# Digital_Encoder_Breakout.net
KiCad netlist of a schematic drawn in Altium Designer
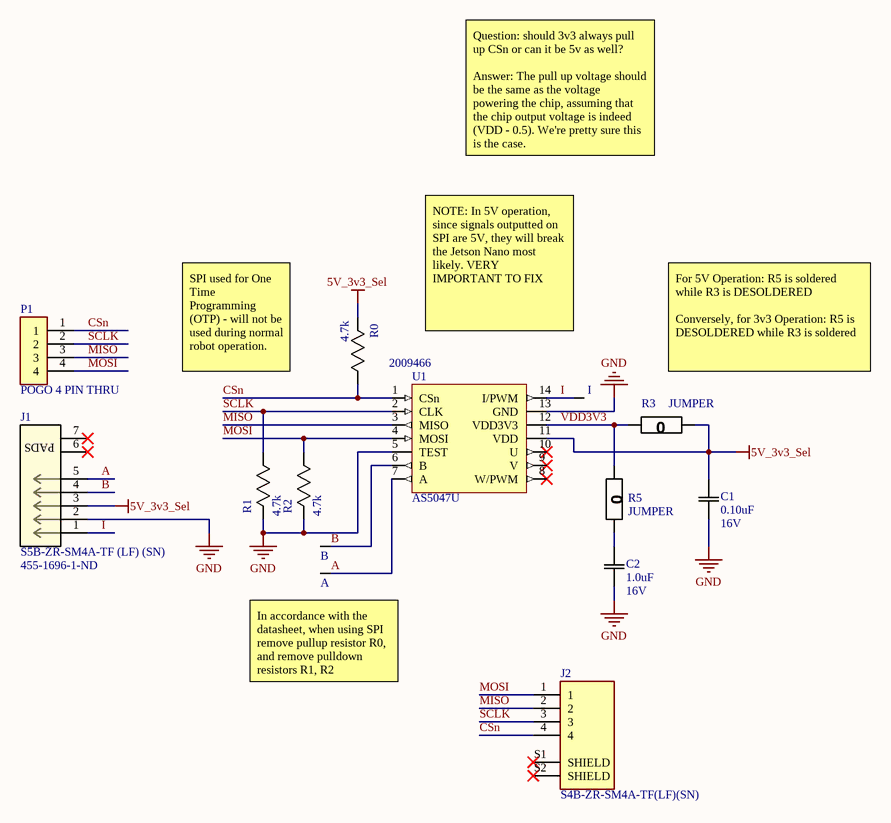
[diagram p0: Digital_Encoder_Breakout.SchDoc]

(export (version "E")
  (design (tool "Eeschema 10.0.6"))
  (components
    (comp (ref "A")
      (value "Test Point (Via)")
      (footprint "TP")
      (libsource (lib "AltiumLibraries") (part "Test Point (Via)"))
    )
    (comp (ref "B")
      (value "Test Point (Via)")
      (footprint "TP")
      (libsource (lib "AltiumLibraries") (part "Test Point (Via)"))
    )
    (comp (ref "C1")
      (value "0.10uF")
      (footprint "0603")
      (description "CAP CER 0.10UF 16V X5R 0603/0805")
      (fields (field (name "TOLERANCE") "10%") (field (name "RATING") "16V"))
      (libsource (lib "AltiumLibraries") (part "CAP 0.10uF 16V"))
    )
    (comp (ref "C2")
      (value "1.0uF")
      (footprint "0603")
      (description "CAP CER 1.0UF 16V X5R 0603/0805")
      (fields (field (name "TOLERANCE") "10%") (field (name "RATING") "16V"))
      (libsource (lib "AltiumLibraries") (part "CAP 1.0uF 16V"))
    )
    (comp (ref "I")
      (value "Test Point (Via)")
      (footprint "TP")
      (libsource (lib "AltiumLibraries") (part "Test Point (Via)"))
    )
    (comp (ref "J1")
      (value "S5B-ZR-SM4A-TF (LF) (SN)")
      (footprint "JST_S5B-ZR-SM4A-TF")
      (description "Connector Header Surface Mount, Right Angle 5 position 0.059\" (1.50mm)")
      (fields
        (field (name "SUPPLIER PART NUMBER 1") "455-1696-1-ND")
        (field (name "COPYRIGHT") "Copyright (C) 2021 Ultra Librarian. All rights reserved.")
      )
      (libsource (lib "AltiumLibraries") (part "CN 5POS JST ZR RA"))
    )
    (comp (ref "J2")
      (value "S4B-ZR-SM4A-TF(LF)(SN)")
      (footprint "JST_S4B-ZR-SM4A-TF(LF)(SN)")
      (description "Connector Header Surface Mount, Right Angle 4 position 0.059 (1.50mm)")
      (fields (field (name "MF") "JST Sales"))
      (libsource (lib "AltiumLibraries") (part "S4B-ZR-SM4A-TF(LF)(SN)"))
    )
    (comp (ref "P1")
      (value "POGO 4 PIN THRU")
      (footprint "POGO 4 PIN THRU")
      (description "4 pin POGO Holes 0.100\" Pitch")
      (libsource (lib "AltiumLibraries") (part "POGO 4 PIN THRU"))
    )
    (comp (ref "R0")
      (value "4.7k")
      (footprint "0603")
      (description "RES SMD 4.7k OHM 5% 1/8W 0805")
      (fields (field (name "TOLERANCE") "5%"))
      (libsource (lib "") (part "RES 4.7k 1/8W - 5%_1"))
    )
    (comp (ref "R1")
      (value "4.7k")
      (footprint "0603")
      (description "RES SMD 4.7k OHM 5% 1/8W 0805")
      (fields (field (name "TOLERANCE") "5%"))
      (libsource (lib "") (part "RES 4.7k 1/8W - 5%_1"))
    )
    (comp (ref "R2")
      (value "4.7k")
      (footprint "0603")
      (description "RES SMD 4.7k OHM 5% 1/8W 0805")
      (fields (field (name "TOLERANCE") "5%"))
      (libsource (lib "AltiumLibraries") (part "RES 4.7k 1/8W - 5%"))
    )
    (comp (ref "R3")
      (value "JUMPER")
      (footprint "0603")
      (description "RES SMD 0 OHM JUMPER GENERIC 0805/0603")
      (libsource (lib "AltiumLibraries") (part "RES 0 JUMPER"))
    )
    (comp (ref "R5")
      (value "JUMPER")
      (footprint "0603")
      (description "RES SMD 0 OHM JUMPER GENERIC 0805/0603")
      (libsource (lib "AltiumLibraries") (part "RES 0 JUMPER"))
    )
    (comp (ref "U1")
      (value "AS5047U")
      (footprint "AS5047U")
      (description "14-Bit On-Axis Magnetic Rotary Position Sensor with Up to 14-Bit Binary Incremental Pulse Count")
      (fields (field (name "SUPPLIER PART NUMBER 1") "2009466"))
      (libsource (lib "AltiumLibraries") (part "AS5047U"))
    )
  )
  (nets
    (net (code "1") (name "/A") (class "Default")
      (node (ref "A") (pin "1") (pinfunction "1_1") (pintype "passive"))
      (node (ref "J1") (pin "5") (pinfunction "5_5") (pintype "passive"))
      (node (ref "U1") (pin "7") (pinfunction "A_7") (pintype "output"))
    )
    (net (code "2") (name "/B") (class "Default")
      (node (ref "B") (pin "1") (pinfunction "1_1") (pintype "passive"))
      (node (ref "J1") (pin "4") (pinfunction "4_4") (pintype "passive"))
      (node (ref "U1") (pin "6") (pinfunction "B_6") (pintype "output"))
    )
    (net (code "3") (name "/CSn") (class "Default")
      (node (ref "J2") (pin "4") (pinfunction "4_4") (pintype "passive"))
      (node (ref "P1") (pin "1") (pinfunction "1_1") (pintype "passive"))
      (node (ref "R0") (pin "1") (pinfunction "R1_1") (pintype "passive"))
      (node (ref "U1") (pin "1") (pinfunction "CSn_1") (pintype "input"))
    )
    (net (code "4") (name "/I") (class "Default")
      (node (ref "I") (pin "1") (pinfunction "1_1") (pintype "passive"))
      (node (ref "J1") (pin "1") (pinfunction "1_1") (pintype "passive"))
      (node (ref "U1") (pin "14") (pinfunction "I/PWM_14") (pintype "output"))
    )
    (net (code "5") (name "/MISO") (class "Default")
      (node (ref "J2") (pin "2") (pinfunction "2_2") (pintype "passive"))
      (node (ref "P1") (pin "3") (pinfunction "3_3") (pintype "passive"))
      (node (ref "U1") (pin "3") (pinfunction "MISO_3") (pintype "output"))
    )
    (net (code "6") (name "/MOSI") (class "Default")
      (node (ref "J2") (pin "1") (pinfunction "1_1") (pintype "passive"))
      (node (ref "P1") (pin "4") (pinfunction "4_4") (pintype "passive"))
      (node (ref "R2") (pin "1") (pinfunction "R1_1") (pintype "passive"))
      (node (ref "U1") (pin "4") (pinfunction "MOSI_4") (pintype "input"))
    )
    (net (code "7") (name "/SCLK") (class "Default")
      (node (ref "J2") (pin "3") (pinfunction "3_3") (pintype "passive"))
      (node (ref "P1") (pin "2") (pinfunction "2_2") (pintype "passive"))
      (node (ref "R1") (pin "1") (pinfunction "R1_1") (pintype "passive"))
      (node (ref "U1") (pin "2") (pinfunction "CLK_2") (pintype "input"))
    )
    (net (code "8") (name "/VDD3V3") (class "Default")
      (node (ref "R3") (pin "2") (pinfunction "R2_2") (pintype "passive"))
      (node (ref "R5") (pin "1") (pinfunction "R1_1") (pintype "passive"))
      (node (ref "U1") (pin "12") (pinfunction "VDD3V3_12") (pintype "passive"))
    )
    (net (code "9") (name "5V_3v3_Sel") (class "Default")
      (node (ref "C1") (pin "2") (pinfunction "C2_2") (pintype "passive"))
      (node (ref "J1") (pin "3") (pinfunction "3_3") (pintype "passive"))
      (node (ref "R0") (pin "2") (pinfunction "R2_2") (pintype "passive"))
      (node (ref "R3") (pin "1") (pinfunction "R1_1") (pintype "passive"))
      (node (ref "U1") (pin "11") (pinfunction "VDD_11") (pintype "passive"))
    )
    (net (code "10") (name "GND") (class "Default")
      (node (ref "C1") (pin "1") (pinfunction "C1_1") (pintype "passive"))
      (node (ref "C2") (pin "2") (pinfunction "C2_2") (pintype "passive"))
      (node (ref "J1") (pin "2") (pinfunction "2_2") (pintype "passive"))
      (node (ref "R1") (pin "2") (pinfunction "R2_2") (pintype "passive"))
      (node (ref "R2") (pin "2") (pinfunction "R2_2") (pintype "passive"))
      (node (ref "U1") (pin "13") (pinfunction "GND_13") (pintype "passive"))
      (node (ref "U1") (pin "5") (pinfunction "TEST_5") (pintype "passive"))
    )
    (net (code "11") (name "Net-(C2-C1)") (class "Default")
      (node (ref "C2") (pin "1") (pinfunction "C1_1") (pintype "passive"))
      (node (ref "R5") (pin "2") (pinfunction "R2_2") (pintype "passive"))
    )
    (net (code "12") (name "unconnected-(J1-Pad6)") (class "Default")
      (node (ref "J1") (pin "6") (pinfunction "6_6") (pintype "passive+no_connect"))
    )
    (net (code "13") (name "unconnected-(J1-Pad7)") (class "Default")
      (node (ref "J1") (pin "7") (pinfunction "7_7") (pintype "passive+no_connect"))
    )
    (net (code "14") (name "unconnected-(J2-SHIELD-PadS1)") (class "Default")
      (node (ref "J2") (pin "S1") (pinfunction "SHIELD_S1") (pintype "passive+no_connect"))
    )
    (net (code "15") (name "unconnected-(J2-SHIELD-PadS2)") (class "Default")
      (node (ref "J2") (pin "S2") (pinfunction "SHIELD_S2") (pintype "passive+no_connect"))
    )
    (net (code "16") (name "unconnected-(U1-U-Pad10)") (class "Default")
      (node (ref "U1") (pin "10") (pinfunction "U_10") (pintype "output+no_connect"))
    )
    (net (code "17") (name "unconnected-(U1-V-Pad9)") (class "Default")
      (node (ref "U1") (pin "9") (pinfunction "V_9") (pintype "output+no_connect"))
    )
    (net (code "18") (name "unconnected-(U1-W{slash}PWM-Pad8)") (class "Default")
      (node (ref "U1") (pin "8") (pinfunction "W/PWM_8") (pintype "output+no_connect"))
    )
  )
)
